# LESR_MainBoard.net
KiCad netlist of a schematic drawn in EAGLE
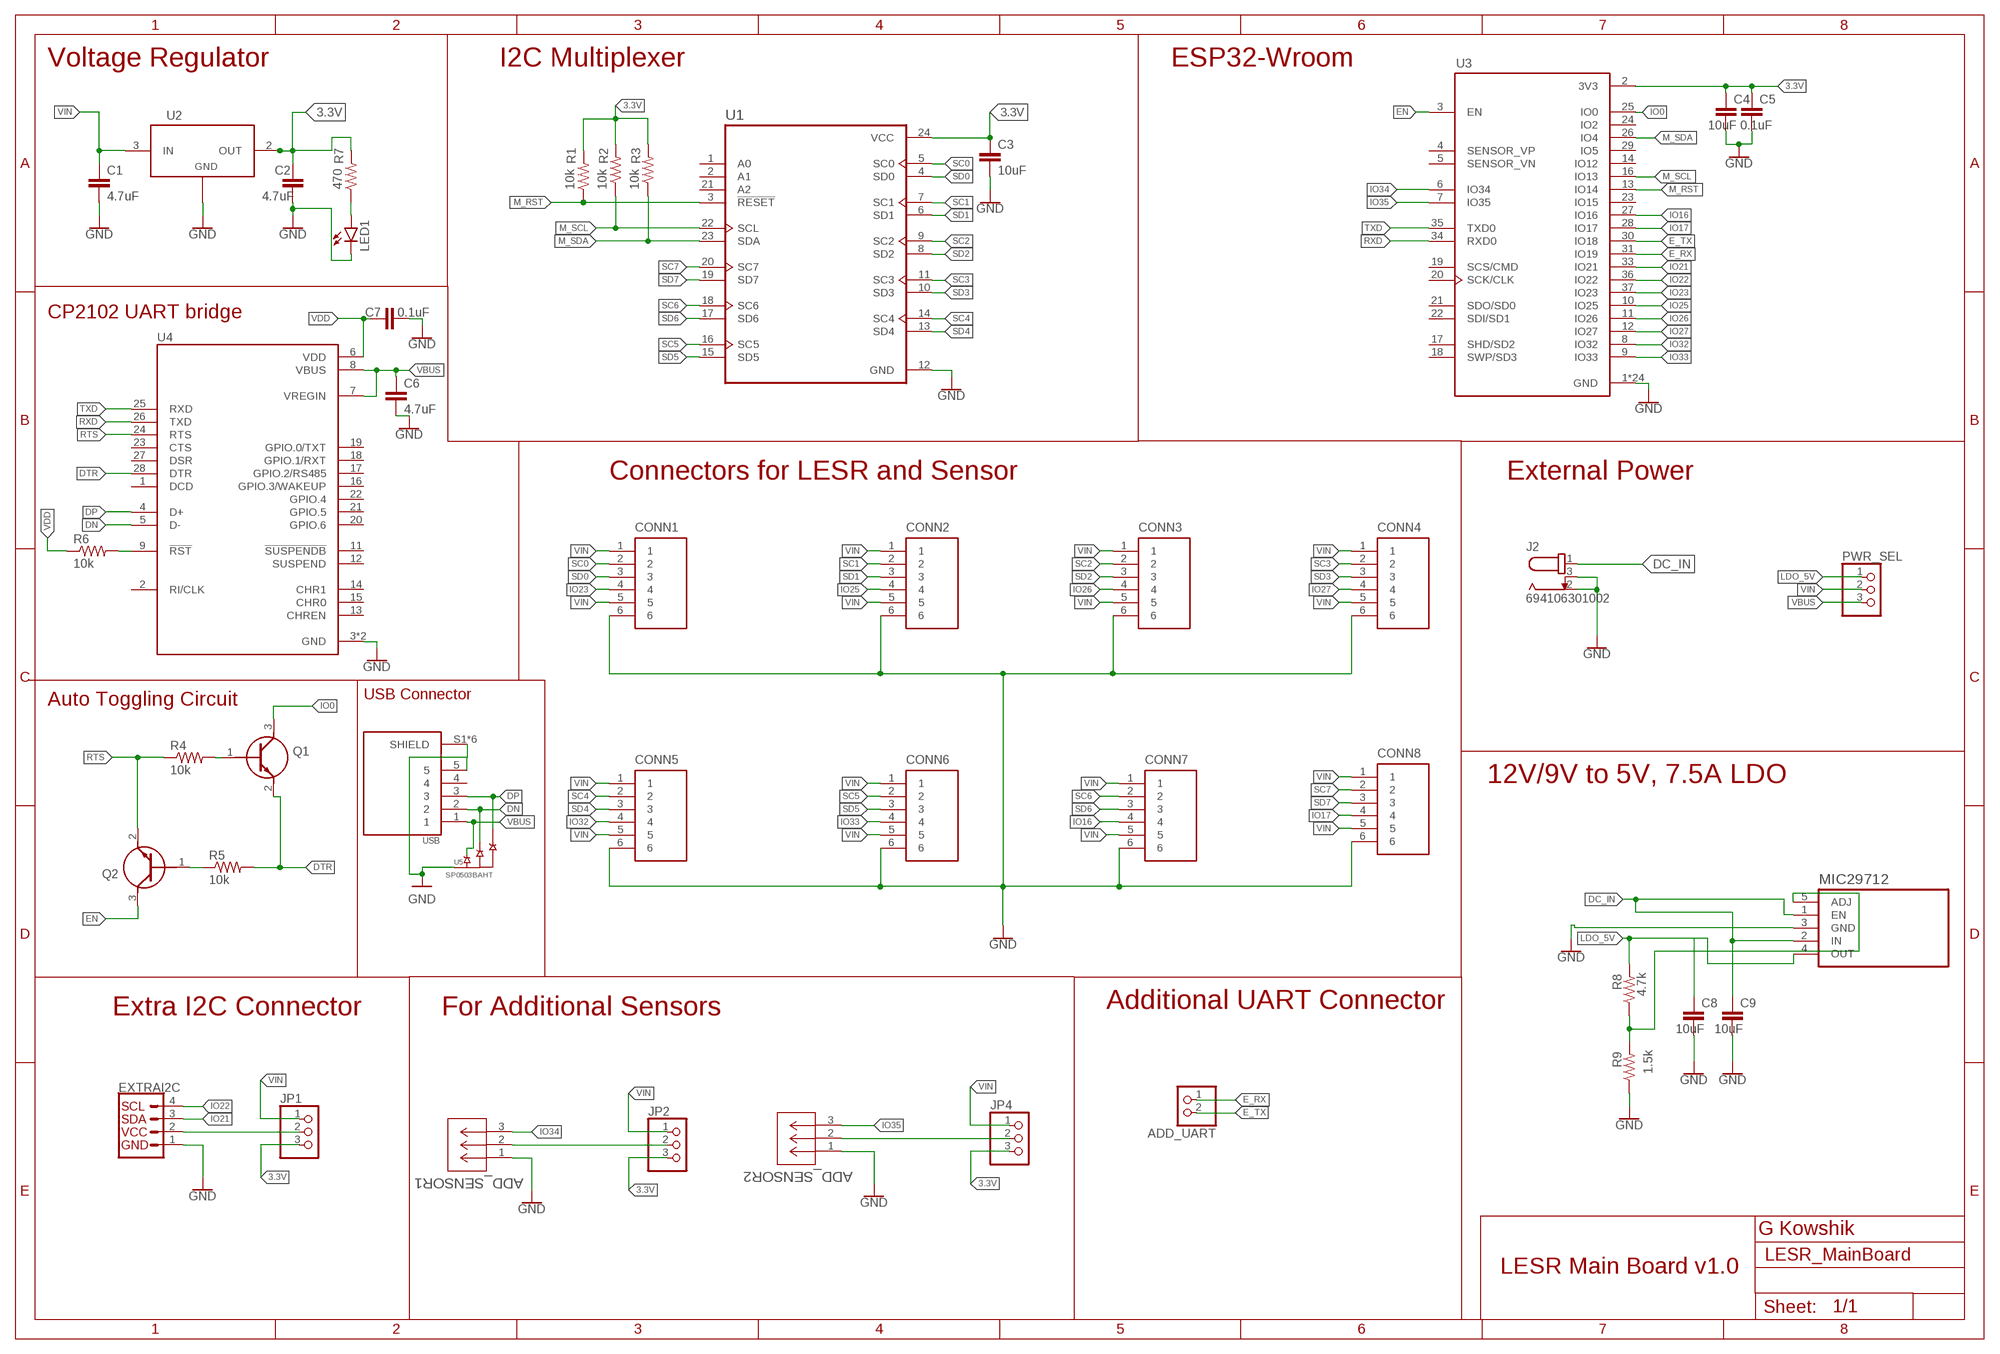
[diagram p0: schematic, sheet 1]

(export (version "E")
  (design (tool "Eeschema 10.0.6"))
  (components
    (comp (ref "ADD_SENSOR1")
      (value "BM03B-SRSS-TB(LF)(SN)")
      (footprint "eagle-import:CONN_BM03B-SRSS-TB(LF)(SN)_JST")
      (fields (field (name "COPYRIGHT") "Copyright (C) 2018 Accelerated Designs. All rights reserved"))
      (libsource (lib "eagle-import") (part "BM03B-SRSS-TB(LF)(SN)"))
    )
    (comp (ref "ADD_SENSOR2")
      (value "BM03B-SRSS-TB(LF)(SN)")
      (footprint "eagle-import:CONN_BM03B-SRSS-TB(LF)(SN)_JST")
      (fields (field (name "COPYRIGHT") "Copyright (C) 2018 Accelerated Designs. All rights reserved"))
      (libsource (lib "eagle-import") (part "BM03B-SRSS-TB(LF)(SN)"))
    )
    (comp (ref "ADD_UART")
      (value "JST_2PIN-SMT")
      (footprint "eagle-import:JST-PH-2-SMT")
      (libsource (lib "eagle-import") (part "JST_2PIN-SMT"))
    )
    (comp (ref "C1")
      (value "4.7uF")
      (footprint "eagle-import:C0805")
      (libsource (lib "eagle-import") (part "C-EUC0805"))
    )
    (comp (ref "C2")
      (value "4.7uF")
      (footprint "eagle-import:C0805")
      (libsource (lib "eagle-import") (part "C-EUC0805"))
    )
    (comp (ref "C3")
      (value "10uF")
      (footprint "eagle-import:C0805")
      (libsource (lib "eagle-import") (part "C-EUC0805"))
    )
    (comp (ref "C4")
      (value "10uF")
      (footprint "eagle-import:C0805")
      (libsource (lib "eagle-import") (part "C-EUC0805"))
    )
    (comp (ref "C5")
      (value "0.1uF")
      (footprint "eagle-import:C0805")
      (libsource (lib "eagle-import") (part "C-EUC0805"))
    )
    (comp (ref "C6")
      (value "4.7uF")
      (footprint "eagle-import:C0805")
      (libsource (lib "eagle-import") (part "C-EUC0805"))
    )
    (comp (ref "C7")
      (value "0.1uF")
      (footprint "eagle-import:C0805")
      (libsource (lib "eagle-import") (part "C-EUC0805"))
    )
    (comp (ref "C8")
      (value "10uF")
      (footprint "eagle-import:C0805")
      (libsource (lib "eagle-import") (part "C-EUC0805"))
    )
    (comp (ref "C9")
      (value "10uF")
      (footprint "eagle-import:C0805")
      (libsource (lib "eagle-import") (part "C-EUC0805"))
    )
    (comp (ref "CONN1")
      (value "JST_6_PIN_VERTICAL")
      (footprint "eagle-import:JST-6-SMD-VERT-1.0MM")
      (libsource (lib "eagle-import") (part "JST_6_PIN_VERTICAL"))
    )
    (comp (ref "CONN2")
      (value "JST_6_PIN_VERTICAL")
      (footprint "eagle-import:JST-6-SMD-VERT-1.0MM")
      (libsource (lib "eagle-import") (part "JST_6_PIN_VERTICAL"))
    )
    (comp (ref "CONN3")
      (value "JST_6_PIN_VERTICAL")
      (footprint "eagle-import:JST-6-SMD-VERT-1.0MM")
      (libsource (lib "eagle-import") (part "JST_6_PIN_VERTICAL"))
    )
    (comp (ref "CONN4")
      (value "JST_6_PIN_VERTICAL")
      (footprint "eagle-import:JST-6-SMD-VERT-1.0MM")
      (libsource (lib "eagle-import") (part "JST_6_PIN_VERTICAL"))
    )
    (comp (ref "CONN5")
      (value "JST_6_PIN_VERTICAL")
      (footprint "eagle-import:JST-6-SMD-VERT-1.0MM")
      (libsource (lib "eagle-import") (part "JST_6_PIN_VERTICAL"))
    )
    (comp (ref "CONN6")
      (value "JST_6_PIN_VERTICAL")
      (footprint "eagle-import:JST-6-SMD-VERT-1.0MM")
      (libsource (lib "eagle-import") (part "JST_6_PIN_VERTICAL"))
    )
    (comp (ref "CONN7")
      (value "JST_6_PIN_VERTICAL")
      (footprint "eagle-import:JST-6-SMD-VERT-1.0MM")
      (libsource (lib "eagle-import") (part "JST_6_PIN_VERTICAL"))
    )
    (comp (ref "CONN8")
      (value "JST_6_PIN_VERTICAL")
      (footprint "eagle-import:JST-6-SMD-VERT-1.0MM")
      (libsource (lib "eagle-import") (part "JST_6_PIN_VERTICAL"))
    )
    (comp (ref "EXTRAI2C")
      (value "Vertical Qwiic Connector")
      (footprint "eagle-import:JST04_1MM_VERT")
      (libsource (lib "eagle-import") (part "QWIIC_CONNECTOR"))
    )
    (comp (ref "J2")
      (value "694106301002")
      (footprint "eagle-import:694106301002")
      (fields
        (field (name "DIGIKEY_PART_NUMBER") "732-5930-ND")
        (field (name "MANUFACTURER") "Wurth Electronics Inc.")
        (field (name "CREATED_BY") "PCBLayout.com")
      )
      (libsource (lib "eagle-import") (part "694106301002"))
    )
    (comp (ref "JP1")
      (value "PINHD-1X3")
      (footprint "eagle-import:1X03")
      (libsource (lib "eagle-import") (part "PINHD-1X3"))
    )
    (comp (ref "JP2")
      (value "PINHD-1X3")
      (footprint "eagle-import:1X03")
      (libsource (lib "eagle-import") (part "PINHD-1X3"))
    )
    (comp (ref "JP4")
      (value "PINHD-1X3")
      (footprint "eagle-import:1X03")
      (libsource (lib "eagle-import") (part "PINHD-1X3"))
    )
    (comp (ref "LED1")
      (value "LEDCHIPLED_0805")
      (footprint "eagle-import:CHIPLED_0805")
      (libsource (lib "eagle-import") (part "LEDCHIPLED_0805"))
    )
    (comp (ref "MIC29712")
      (value "MIC29712WT")
      (footprint "eagle-import:TO170P1066X482X1572-5")
      (fields (field (name "MF") "Microchip"))
      (libsource (lib "eagle-import") (part "MIC29712WT"))
    )
    (comp (ref "PWR_SEL")
      (value "PINHD-1X3")
      (footprint "eagle-import:1X03")
      (libsource (lib "eagle-import") (part "PINHD-1X3"))
    )
    (comp (ref "Q1")
      (value "SS8050-G")
      (footprint "eagle-import:SOT95P240X115-3N")
      (fields (field (name "MF") "Comchip Technology"))
      (libsource (lib "eagle-import") (part "SS8050-G"))
    )
    (comp (ref "Q2")
      (value "SS8050-G")
      (footprint "eagle-import:SOT95P240X115-3N")
      (fields (field (name "MF") "Comchip Technology"))
      (libsource (lib "eagle-import") (part "SS8050-G"))
    )
    (comp (ref "R1")
      (value "10k")
      (footprint "eagle-import:R0805")
      (libsource (lib "eagle-import") (part "R-US_R0805"))
    )
    (comp (ref "R2")
      (value "10k")
      (footprint "eagle-import:R0805")
      (libsource (lib "eagle-import") (part "R-US_R0805"))
    )
    (comp (ref "R3")
      (value "10k")
      (footprint "eagle-import:R0805")
      (libsource (lib "eagle-import") (part "R-US_R0805"))
    )
    (comp (ref "R4")
      (value "10k")
      (footprint "eagle-import:R0805")
      (libsource (lib "eagle-import") (part "R-US_R0805"))
    )
    (comp (ref "R5")
      (value "10k")
      (footprint "eagle-import:R0805")
      (libsource (lib "eagle-import") (part "R-US_R0805"))
    )
    (comp (ref "R6")
      (value "10k")
      (footprint "eagle-import:R0805")
      (libsource (lib "eagle-import") (part "R-US_R0805"))
    )
    (comp (ref "R7")
      (value "470")
      (footprint "eagle-import:R0805")
      (libsource (lib "eagle-import") (part "R-US_R0805"))
    )
    (comp (ref "R8")
      (value "4.7k")
      (footprint "eagle-import:R0805")
      (libsource (lib "eagle-import") (part "R-US_R0805"))
    )
    (comp (ref "R9")
      (value "1.5k")
      (footprint "eagle-import:R0805")
      (libsource (lib "eagle-import") (part "R-US_R0805"))
    )
    (comp (ref "U1")
      (value "TCA9548APWR")
      (footprint "eagle-import:SOP65P640X120-24N")
      (fields (field (name "MF") "Texas Instruments"))
      (libsource (lib "eagle-import") (part "TCA9548APWR"))
    )
    (comp (ref "U2")
      (value "NCP1117ST33T3G")
      (footprint "eagle-import:SOT-223")
      (fields
        (field (name "DIGIKEY_PART_NUMBER") "NCP1117ST33T3GOSTR-ND")
        (field (name "MANUFACTURER") "ON Semiconductor")
        (field (name "CREATED_BY") "PCBLayout.com")
      )
      (libsource (lib "eagle-import") (part "NCP1117ST33T3G"))
    )
    (comp (ref "U3")
      (value "ESP32-WROOM-32")
      (footprint "eagle-import:MODULE_ESP32-WROOM-32")
      (fields (field (name "MF") "Espressif Systems"))
      (libsource (lib "eagle-import") (part "ESP32-WROOM-32"))
    )
    (comp (ref "U4")
      (value "CP2102N-A01-GQFN28")
      (footprint "eagle-import:QFN50P500X500X80-29N")
      (fields (field (name "MF") "Silicon Labs"))
      (libsource (lib "eagle-import") (part "CP2102N-A01-GQFN28"))
    )
    (comp (ref "U5")
      (value "SP0503BAHT")
      (footprint "eagle-import:SOT143")
      (fields (field (name "MF") "Littelfuse Inc."))
      (libsource (lib "eagle-import") (part "SP0503BAHT"))
    )
    (comp (ref "USB")
      (value "10118194-0001LF")
      (footprint "eagle-import:AMPHENOL_10118194-0001LF")
      (fields (field (name "MF") "Amphenol ICC (FCI)"))
      (libsource (lib "eagle-import") (part "10118194-0001LF"))
    )
  )
  (nets
    (net (code "1") (name "3.3V") (class "Default")
      (node (ref "C2") (pin "1") (pinfunction "1_1") (pintype "passive"))
      (node (ref "C3") (pin "1") (pinfunction "1_1") (pintype "passive"))
      (node (ref "C4") (pin "1") (pinfunction "1_1") (pintype "passive"))
      (node (ref "C5") (pin "1") (pinfunction "1_1") (pintype "passive"))
      (node (ref "JP1") (pin "3") (pinfunction "3_3") (pintype "passive"))
      (node (ref "JP2") (pin "3") (pinfunction "3_3") (pintype "passive"))
      (node (ref "JP4") (pin "3") (pinfunction "3_3") (pintype "passive"))
      (node (ref "R1") (pin "2") (pinfunction "2_2") (pintype "passive"))
      (node (ref "R2") (pin "2") (pinfunction "2_2") (pintype "passive"))
      (node (ref "R3") (pin "2") (pinfunction "2_2") (pintype "passive"))
      (node (ref "R7") (pin "2") (pinfunction "2_2") (pintype "passive"))
      (node (ref "U1") (pin "24") (pinfunction "VCC_24") (pintype "power_in"))
      (node (ref "U2") (pin "2") (pinfunction "OUT_2") (pintype "output"))
      (node (ref "U2") (pin "4") (pinfunction "4_4") (pintype "passive"))
      (node (ref "U3") (pin "2") (pinfunction "3V3_2") (pintype "power_in"))
    )
    (net (code "2") (name "DC_IN") (class "Default")
      (node (ref "C9") (pin "1") (pinfunction "1_1") (pintype "passive"))
      (node (ref "J2") (pin "1") (pinfunction "1_1") (pintype "passive"))
      (node (ref "MIC29712") (pin "1") (pinfunction "EN_1") (pintype "input"))
      (node (ref "MIC29712") (pin "2") (pinfunction "IN_2") (pintype "input"))
    )
    (net (code "3") (name "DN") (class "Default")
      (node (ref "U4") (pin "5") (pinfunction "D-_5") (pintype "bidirectional"))
      (node (ref "U5") (pin "3") (pinfunction "B_3") (pintype "bidirectional"))
      (node (ref "USB") (pin "2") (pinfunction "2_2") (pintype "passive"))
    )
    (net (code "4") (name "DP") (class "Default")
      (node (ref "U4") (pin "4") (pinfunction "D+_4") (pintype "bidirectional"))
      (node (ref "U5") (pin "4") (pinfunction "C_4") (pintype "bidirectional"))
      (node (ref "USB") (pin "3") (pinfunction "3_3") (pintype "passive"))
    )
    (net (code "5") (name "DTR") (class "Default")
      (node (ref "Q1") (pin "2") (pinfunction "E_2") (pintype "bidirectional"))
      (node (ref "R5") (pin "2") (pinfunction "2_2") (pintype "passive"))
      (node (ref "U4") (pin "28") (pinfunction "DTR_28") (pintype "output"))
    )
    (net (code "6") (name "EN") (class "Default")
      (node (ref "Q2") (pin "3") (pinfunction "C_3") (pintype "bidirectional"))
      (node (ref "U3") (pin "3") (pinfunction "EN_3") (pintype "input"))
    )
    (net (code "7") (name "E_RX") (class "Default")
      (node (ref "ADD_UART") (pin "1") (pinfunction "2_1") (pintype "passive"))
      (node (ref "U3") (pin "31") (pinfunction "IO19_31") (pintype "bidirectional"))
    )
    (net (code "8") (name "E_TX") (class "Default")
      (node (ref "ADD_UART") (pin "2") (pinfunction "1_2") (pintype "passive"))
      (node (ref "U3") (pin "30") (pinfunction "IO18_30") (pintype "bidirectional"))
    )
    (net (code "9") (name "GND") (class "Default")
      (node (ref "ADD_SENSOR1") (pin "1") (pinfunction "1_1") (pintype "passive"))
      (node (ref "ADD_SENSOR2") (pin "1") (pinfunction "1_1") (pintype "passive"))
      (node (ref "C1") (pin "2") (pinfunction "2_2") (pintype "passive"))
      (node (ref "C2") (pin "2") (pinfunction "2_2") (pintype "passive"))
      (node (ref "C3") (pin "2") (pinfunction "2_2") (pintype "passive"))
      (node (ref "C4") (pin "2") (pinfunction "2_2") (pintype "passive"))
      (node (ref "C5") (pin "2") (pinfunction "2_2") (pintype "passive"))
      (node (ref "C6") (pin "2") (pinfunction "2_2") (pintype "passive"))
      (node (ref "C7") (pin "2") (pinfunction "2_2") (pintype "passive"))
      (node (ref "C8") (pin "2") (pinfunction "2_2") (pintype "passive"))
      (node (ref "C9") (pin "2") (pinfunction "2_2") (pintype "passive"))
      (node (ref "CONN1") (pin "6") (pinfunction "6_6") (pintype "bidirectional"))
      (node (ref "CONN2") (pin "6") (pinfunction "6_6") (pintype "bidirectional"))
      (node (ref "CONN3") (pin "6") (pinfunction "6_6") (pintype "bidirectional"))
      (node (ref "CONN4") (pin "6") (pinfunction "6_6") (pintype "bidirectional"))
      (node (ref "CONN5") (pin "6") (pinfunction "6_6") (pintype "bidirectional"))
      (node (ref "CONN6") (pin "6") (pinfunction "6_6") (pintype "bidirectional"))
      (node (ref "CONN7") (pin "6") (pinfunction "6_6") (pintype "bidirectional"))
      (node (ref "CONN8") (pin "6") (pinfunction "6_6") (pintype "bidirectional"))
      (node (ref "EXTRAI2C") (pin "1") (pinfunction "1_1") (pintype "power_in"))
      (node (ref "J2") (pin "2") (pinfunction "2_2") (pintype "passive"))
      (node (ref "J2") (pin "3") (pinfunction "3_3") (pintype "passive"))
      (node (ref "LED1") (pin "C") (pinfunction "C_C") (pintype "passive"))
      (node (ref "MIC29712") (pin "3") (pinfunction "GND_3") (pintype "input"))
      (node (ref "R9") (pin "1") (pinfunction "1_1") (pintype "passive"))
      (node (ref "U1") (pin "12") (pinfunction "GND_12") (pintype "power_in"))
      (node (ref "U2") (pin "1") (pinfunction "ADJ/GND_1") (pintype "power_in"))
      (node (ref "U3") (pin "1") (pinfunction "GND_1") (pintype "power_in"))
      (node (ref "U3") (pin "15") (pinfunction "GND_15") (pintype "power_in"))
      (node (ref "U3") (pin "38") (pinfunction "GND_38") (pintype "power_in"))
      (node (ref "U3") (pin "39_1") (pinfunction "GND_39_1") (pintype "power_in"))
      (node (ref "U3") (pin "39_10") (pinfunction "GND_39_10") (pintype "power_in"))
      (node (ref "U3") (pin "39_11") (pinfunction "GND_39_11") (pintype "power_in"))
      (node (ref "U3") (pin "39_12") (pinfunction "GND_39_12") (pintype "power_in"))
      (node (ref "U3") (pin "39_13") (pinfunction "GND_39_13") (pintype "power_in"))
      (node (ref "U3") (pin "39_14") (pinfunction "GND_39_14") (pintype "power_in"))
      (node (ref "U3") (pin "39_15") (pinfunction "GND_39_15") (pintype "power_in"))
      (node (ref "U3") (pin "39_16") (pinfunction "GND_39_16") (pintype "power_in"))
      (node (ref "U3") (pin "39_17") (pinfunction "GND_39_17") (pintype "power_in"))
      (node (ref "U3") (pin "39_18") (pinfunction "GND_39_18") (pintype "power_in"))
      (node (ref "U3") (pin "39_19") (pinfunction "GND_39_19") (pintype "power_in"))
      (node (ref "U3") (pin "39_2") (pinfunction "GND_39_2") (pintype "power_in"))
      (node (ref "U3") (pin "39_20") (pinfunction "GND_39_20") (pintype "power_in"))
      (node (ref "U3") (pin "39_21") (pinfunction "GND_39_21") (pintype "power_in"))
      (node (ref "U3") (pin "39_3") (pinfunction "GND_39_3") (pintype "power_in"))
      (node (ref "U3") (pin "39_4") (pinfunction "GND_39_4") (pintype "power_in"))
      (node (ref "U3") (pin "39_5") (pinfunction "GND_39_5") (pintype "power_in"))
      (node (ref "U3") (pin "39_6") (pinfunction "GND_39_6") (pintype "power_in"))
      (node (ref "U3") (pin "39_7") (pinfunction "GND_39_7") (pintype "power_in"))
      (node (ref "U3") (pin "39_8") (pinfunction "GND_39_8") (pintype "power_in"))
      (node (ref "U3") (pin "39_9") (pinfunction "GND_39_9") (pintype "power_in"))
      (node (ref "U4") (pin "29") (pinfunction "GND_29") (pintype "power_in"))
      (node (ref "U4") (pin "3") (pinfunction "GND_3") (pintype "power_in"))
      (node (ref "U5") (pin "1") (pinfunction "GND_1") (pintype "bidirectional"))
      (node (ref "USB") (pin "5") (pinfunction "5_5") (pintype "passive"))
      (node (ref "USB") (pin "S1") (pinfunction "SHIELD_S1") (pintype "passive"))
      (node (ref "USB") (pin "S2") (pinfunction "SHIELD_S2") (pintype "passive"))
      (node (ref "USB") (pin "S3") (pinfunction "SHIELD_S3") (pintype "passive"))
      (node (ref "USB") (pin "S4") (pinfunction "SHIELD_S4") (pintype "passive"))
      (node (ref "USB") (pin "S5") (pinfunction "SHIELD_S5") (pintype "passive"))
      (node (ref "USB") (pin "S6") (pinfunction "SHIELD_S6") (pintype "passive"))
    )
    (net (code "10") (name "IO0") (class "Default")
      (node (ref "Q1") (pin "3") (pinfunction "C_3") (pintype "bidirectional"))
      (node (ref "U3") (pin "25") (pinfunction "IO0_25") (pintype "bidirectional"))
    )
    (net (code "11") (name "IO16") (class "Default")
      (node (ref "CONN7") (pin "4") (pinfunction "4_4") (pintype "bidirectional"))
      (node (ref "U3") (pin "27") (pinfunction "IO16_27") (pintype "bidirectional"))
    )
    (net (code "12") (name "IO17") (class "Default")
      (node (ref "CONN8") (pin "4") (pinfunction "4_4") (pintype "bidirectional"))
      (node (ref "U3") (pin "28") (pinfunction "IO17_28") (pintype "bidirectional"))
    )
    (net (code "13") (name "IO21") (class "Default")
      (node (ref "EXTRAI2C") (pin "3") (pinfunction "3_3") (pintype "passive"))
      (node (ref "U3") (pin "33") (pinfunction "IO21_33") (pintype "bidirectional"))
    )
    (net (code "14") (name "IO22") (class "Default")
      (node (ref "EXTRAI2C") (pin "4") (pinfunction "4_4") (pintype "passive"))
      (node (ref "U3") (pin "36") (pinfunction "IO22_36") (pintype "bidirectional"))
    )
    (net (code "15") (name "IO23") (class "Default")
      (node (ref "CONN1") (pin "4") (pinfunction "4_4") (pintype "bidirectional"))
      (node (ref "U3") (pin "37") (pinfunction "IO23_37") (pintype "bidirectional"))
    )
    (net (code "16") (name "IO25") (class "Default")
      (node (ref "CONN2") (pin "4") (pinfunction "4_4") (pintype "bidirectional"))
      (node (ref "U3") (pin "10") (pinfunction "IO25_10") (pintype "bidirectional"))
    )
    (net (code "17") (name "IO26") (class "Default")
      (node (ref "CONN3") (pin "4") (pinfunction "4_4") (pintype "bidirectional"))
      (node (ref "U3") (pin "11") (pinfunction "IO26_11") (pintype "bidirectional"))
    )
    (net (code "18") (name "IO27") (class "Default")
      (node (ref "CONN4") (pin "4") (pinfunction "4_4") (pintype "bidirectional"))
      (node (ref "U3") (pin "12") (pinfunction "IO27_12") (pintype "bidirectional"))
    )
    (net (code "19") (name "IO32") (class "Default")
      (node (ref "CONN5") (pin "4") (pinfunction "4_4") (pintype "bidirectional"))
      (node (ref "U3") (pin "8") (pinfunction "IO32_8") (pintype "bidirectional"))
    )
    (net (code "20") (name "IO33") (class "Default")
      (node (ref "CONN6") (pin "4") (pinfunction "4_4") (pintype "bidirectional"))
      (node (ref "U3") (pin "9") (pinfunction "IO33_9") (pintype "bidirectional"))
    )
    (net (code "21") (name "IO34") (class "Default")
      (node (ref "ADD_SENSOR1") (pin "3") (pinfunction "3_3") (pintype "passive"))
      (node (ref "U3") (pin "6") (pinfunction "IO34_6") (pintype "input"))
    )
    (net (code "22") (name "IO35") (class "Default")
      (node (ref "ADD_SENSOR2") (pin "3") (pinfunction "3_3") (pintype "passive"))
      (node (ref "U3") (pin "7") (pinfunction "IO35_7") (pintype "input"))
    )
    (net (code "23") (name "LDO_5V") (class "Default")
      (node (ref "C8") (pin "1") (pinfunction "1_1") (pintype "passive"))
      (node (ref "MIC29712") (pin "4") (pinfunction "OUT_4") (pintype "input"))
      (node (ref "PWR_SEL") (pin "1") (pinfunction "1_1") (pintype "passive"))
      (node (ref "R8") (pin "2") (pinfunction "2_2") (pintype "passive"))
    )
    (net (code "24") (name "M_RST") (class "Default")
      (node (ref "R1") (pin "1") (pinfunction "1_1") (pintype "passive"))
      (node (ref "U1") (pin "3") (pinfunction "~{RESET}_3") (pintype "input"))
      (node (ref "U3") (pin "13") (pinfunction "IO14_13") (pintype "bidirectional"))
    )
    (net (code "25") (name "M_SCL") (class "Default")
      (node (ref "R2") (pin "1") (pinfunction "1_1") (pintype "passive"))
      (node (ref "U1") (pin "22") (pinfunction "SCL_22") (pintype "bidirectional"))
      (node (ref "U3") (pin "16") (pinfunction "IO13_16") (pintype "bidirectional"))
    )
    (net (code "26") (name "M_SDA") (class "Default")
      (node (ref "R3") (pin "1") (pinfunction "1_1") (pintype "passive"))
      (node (ref "U1") (pin "23") (pinfunction "SDA_23") (pintype "bidirectional"))
      (node (ref "U3") (pin "26") (pinfunction "IO4_26") (pintype "bidirectional"))
    )
    (net (code "27") (name "Net-(ADD_SENSOR1-Pad2)") (class "Default")
      (node (ref "ADD_SENSOR1") (pin "2") (pinfunction "2_2") (pintype "passive"))
      (node (ref "JP2") (pin "2") (pinfunction "2_2") (pintype "passive"))
    )
    (net (code "28") (name "Net-(ADD_SENSOR2-Pad2)") (class "Default")
      (node (ref "ADD_SENSOR2") (pin "2") (pinfunction "2_2") (pintype "passive"))
      (node (ref "JP4") (pin "2") (pinfunction "2_2") (pintype "passive"))
    )
    (net (code "29") (name "Net-(EXTRAI2C-Pad2)") (class "Default")
      (node (ref "EXTRAI2C") (pin "2") (pinfunction "2_2") (pintype "power_in"))
      (node (ref "JP1") (pin "2") (pinfunction "2_2") (pintype "passive"))
    )
    (net (code "30") (name "Net-(LED1-PadA)") (class "Default")
      (node (ref "LED1") (pin "A") (pinfunction "A_A") (pintype "passive"))
      (node (ref "R7") (pin "1") (pinfunction "1_1") (pintype "passive"))
    )
    (net (code "31") (name "Net-(MIC29712-ADJ)") (class "Default")
      (node (ref "MIC29712") (pin "5") (pinfunction "ADJ_5") (pintype "input"))
      (node (ref "R8") (pin "1") (pinfunction "1_1") (pintype "passive"))
      (node (ref "R9") (pin "2") (pinfunction "2_2") (pintype "passive"))
    )
    (net (code "32") (name "Net-(Q1-B)") (class "Default")
      (node (ref "Q1") (pin "1") (pinfunction "B_1") (pintype "bidirectional"))
      (node (ref "R4") (pin "2") (pinfunction "2_2") (pintype "passive"))
    )
    (net (code "33") (name "Net-(Q2-B)") (class "Default")
      (node (ref "Q2") (pin "1") (pinfunction "B_1") (pintype "bidirectional"))
      (node (ref "R5") (pin "1") (pinfunction "1_1") (pintype "passive"))
    )
    (net (code "34") (name "Net-(U4-~{RST})") (class "Default")
      (node (ref "R6") (pin "2") (pinfunction "2_2") (pintype "passive"))
      (node (ref "U4") (pin "9") (pinfunction "~{RST}_9") (pintype "input"))
    )
    (net (code "35") (name "RTS") (class "Default")
      (node (ref "Q2") (pin "2") (pinfunction "E_2") (pintype "bidirectional"))
      (node (ref "R4") (pin "1") (pinfunction "1_1") (pintype "passive"))
      (node (ref "U4") (pin "24") (pinfunction "RTS_24") (pintype "output"))
    )
    (net (code "36") (name "RXD") (class "Default")
      (node (ref "U3") (pin "34") (pinfunction "RXD0_34") (pintype "bidirectional"))
      (node (ref "U4") (pin "26") (pinfunction "TXD_26") (pintype "output"))
    )
    (net (code "37") (name "SC0") (class "Default")
      (node (ref "CONN1") (pin "2") (pinfunction "2_2") (pintype "bidirectional"))
      (node (ref "U1") (pin "5") (pinfunction "SC0_5") (pintype "bidirectional"))
    )
    (net (code "38") (name "SC1") (class "Default")
      (node (ref "CONN2") (pin "2") (pinfunction "2_2") (pintype "bidirectional"))
      (node (ref "U1") (pin "7") (pinfunction "SC1_7") (pintype "bidirectional"))
    )
    (net (code "39") (name "SC2") (class "Default")
      (node (ref "CONN3") (pin "2") (pinfunction "2_2") (pintype "bidirectional"))
      (node (ref "U1") (pin "9") (pinfunction "SC2_9") (pintype "bidirectional"))
    )
    (net (code "40") (name "SC3") (class "Default")
      (node (ref "CONN4") (pin "2") (pinfunction "2_2") (pintype "bidirectional"))
      (node (ref "U1") (pin "11") (pinfunction "SC3_11") (pintype "bidirectional"))
    )
    (net (code "41") (name "SC4") (class "Default")
      (node (ref "CONN5") (pin "2") (pinfunction "2_2") (pintype "bidirectional"))
      (node (ref "U1") (pin "14") (pinfunction "SC4_14") (pintype "bidirectional"))
    )
    (net (code "42") (name "SC5") (class "Default")
      (node (ref "CONN6") (pin "2") (pinfunction "2_2") (pintype "bidirectional"))
      (node (ref "U1") (pin "16") (pinfunction "SC5_16") (pintype "bidirectional"))
    )
    (net (code "43") (name "SC6") (class "Default")
      (node (ref "CONN7") (pin "2") (pinfunction "2_2") (pintype "bidirectional"))
      (node (ref "U1") (pin "18") (pinfunction "SC6_18") (pintype "bidirectional"))
    )
    (net (code "44") (name "SC7") (class "Default")
      (node (ref "CONN8") (pin "2") (pinfunction "2_2") (pintype "bidirectional"))
      (node (ref "U1") (pin "20") (pinfunction "SC7_20") (pintype "bidirectional"))
    )
    (net (code "45") (name "SD0") (class "Default")
      (node (ref "CONN1") (pin "3") (pinfunction "3_3") (pintype "bidirectional"))
      (node (ref "U1") (pin "4") (pinfunction "SD0_4") (pintype "bidirectional"))
    )
    (net (code "46") (name "SD1") (class "Default")
      (node (ref "CONN2") (pin "3") (pinfunction "3_3") (pintype "bidirectional"))
      (node (ref "U1") (pin "6") (pinfunction "SD1_6") (pintype "bidirectional"))
    )
    (net (code "47") (name "SD2") (class "Default")
      (node (ref "CONN3") (pin "3") (pinfunction "3_3") (pintype "bidirectional"))
      (node (ref "U1") (pin "8") (pinfunction "SD2_8") (pintype "bidirectional"))
    )
    (net (code "48") (name "SD3") (class "Default")
      (node (ref "CONN4") (pin "3") (pinfunction "3_3") (pintype "bidirectional"))
      (node (ref "U1") (pin "10") (pinfunction "SD3_10") (pintype "bidirectional"))
    )
    (net (code "49") (name "SD4") (class "Default")
      (node (ref "CONN5") (pin "3") (pinfunction "3_3") (pintype "bidirectional"))
      (node (ref "U1") (pin "13") (pinfunction "SD4_13") (pintype "bidirectional"))
    )
    (net (code "50") (name "SD5") (class "Default")
      (node (ref "CONN6") (pin "3") (pinfunction "3_3") (pintype "bidirectional"))
      (node (ref "U1") (pin "15") (pinfunction "SD5_15") (pintype "bidirectional"))
    )
    (net (code "51") (name "SD6") (class "Default")
      (node (ref "CONN7") (pin "3") (pinfunction "3_3") (pintype "bidirectional"))
      (node (ref "U1") (pin "17") (pinfunction "SD6_17") (pintype "bidirectional"))
    )
    (net (code "52") (name "SD7") (class "Default")
      (node (ref "CONN8") (pin "3") (pinfunction "3_3") (pintype "bidirectional"))
      (node (ref "U1") (pin "19") (pinfunction "SD7_19") (pintype "bidirectional"))
    )
    (net (code "53") (name "TXD") (class "Default")
      (node (ref "U3") (pin "35") (pinfunction "TXD0_35") (pintype "bidirectional"))
      (node (ref "U4") (pin "25") (pinfunction "RXD_25") (pintype "input"))
    )
    (net (code "54") (name "VBUS") (class "Default")
      (node (ref "C6") (pin "1") (pinfunction "1_1") (pintype "passive"))
      (node (ref "PWR_SEL") (pin "3") (pinfunction "3_3") (pintype "passive"))
      (node (ref "U4") (pin "7") (pinfunction "VREGIN_7") (pintype "power_in"))
      (node (ref "U4") (pin "8") (pinfunction "VBUS_8") (pintype "power_in"))
      (node (ref "U5") (pin "2") (pinfunction "A_2") (pintype "bidirectional"))
      (node (ref "USB") (pin "1") (pinfunction "1_1") (pintype "passive"))
    )
    (net (code "55") (name "VDD") (class "Default")
      (node (ref "C7") (pin "1") (pinfunction "1_1") (pintype "passive"))
      (node (ref "R6") (pin "1") (pinfunction "1_1") (pintype "passive"))
      (node (ref "U4") (pin "6") (pinfunction "VDD_6") (pintype "power_in"))
    )
    (net (code "56") (name "VIN") (class "Default")
      (node (ref "C1") (pin "1") (pinfunction "1_1") (pintype "passive"))
      (node (ref "CONN1") (pin "1") (pinfunction "1_1") (pintype "bidirectional"))
      (node (ref "CONN1") (pin "5") (pinfunction "5_5") (pintype "bidirectional"))
      (node (ref "CONN2") (pin "1") (pinfunction "1_1") (pintype "bidirectional"))
      (node (ref "CONN2") (pin "5") (pinfunction "5_5") (pintype "bidirectional"))
      (node (ref "CONN3") (pin "1") (pinfunction "1_1") (pintype "bidirectional"))
      (node (ref "CONN3") (pin "5") (pinfunction "5_5") (pintype "bidirectional"))
      (node (ref "CONN4") (pin "1") (pinfunction "1_1") (pintype "bidirectional"))
      (node (ref "CONN4") (pin "5") (pinfunction "5_5") (pintype "bidirectional"))
      (node (ref "CONN5") (pin "1") (pinfunction "1_1") (pintype "bidirectional"))
      (node (ref "CONN5") (pin "5") (pinfunction "5_5") (pintype "bidirectional"))
      (node (ref "CONN6") (pin "1") (pinfunction "1_1") (pintype "bidirectional"))
      (node (ref "CONN6") (pin "5") (pinfunction "5_5") (pintype "bidirectional"))
      (node (ref "CONN7") (pin "1") (pinfunction "1_1") (pintype "bidirectional"))
      (node (ref "CONN7") (pin "5") (pinfunction "5_5") (pintype "bidirectional"))
      (node (ref "CONN8") (pin "1") (pinfunction "1_1") (pintype "bidirectional"))
      (node (ref "CONN8") (pin "5") (pinfunction "5_5") (pintype "bidirectional"))
      (node (ref "JP1") (pin "1") (pinfunction "1_1") (pintype "passive"))
      (node (ref "JP2") (pin "1") (pinfunction "1_1") (pintype "passive"))
      (node (ref "JP4") (pin "1") (pinfunction "1_1") (pintype "passive"))
      (node (ref "PWR_SEL") (pin "2") (pinfunction "2_2") (pintype "passive"))
      (node (ref "U2") (pin "3") (pinfunction "IN_3") (pintype "input"))
    )
    (net (code "57") (name "unconnected-(U1-A0-Pad1)") (class "Default")
      (node (ref "U1") (pin "1") (pinfunction "A0_1") (pintype "input"))
    )
    (net (code "58") (name "unconnected-(U1-A1-Pad2)") (class "Default")
      (node (ref "U1") (pin "2") (pinfunction "A1_2") (pintype "input"))
    )
    (net (code "59") (name "unconnected-(U1-A2-Pad21)") (class "Default")
      (node (ref "U1") (pin "21") (pinfunction "A2_21") (pintype "input"))
    )
    (net (code "60") (name "unconnected-(U3-IO2-Pad24)") (class "Default")
      (node (ref "U3") (pin "24") (pinfunction "IO2_24") (pintype "bidirectional"))
    )
    (net (code "61") (name "unconnected-(U3-IO5-Pad29)") (class "Default")
      (node (ref "U3") (pin "29") (pinfunction "IO5_29") (pintype "bidirectional"))
    )
    (net (code "62") (name "unconnected-(U3-IO12-Pad14)") (class "Default")
      (node (ref "U3") (pin "14") (pinfunction "IO12_14") (pintype "bidirectional"))
    )
    (net (code "63") (name "unconnected-(U3-IO15-Pad23)") (class "Default")
      (node (ref "U3") (pin "23") (pinfunction "IO15_23") (pintype "bidirectional"))
    )
    (net (code "64") (name "unconnected-(U3-SCK{slash}CLK-Pad20)") (class "Default")
      (node (ref "U3") (pin "20") (pinfunction "SCK/CLK_20") (pintype "bidirectional"))
    )
    (net (code "65") (name "unconnected-(U3-SCS{slash}CMD-Pad19)") (class "Default")
      (node (ref "U3") (pin "19") (pinfunction "SCS/CMD_19") (pintype "bidirectional"))
    )
    (net (code "66") (name "unconnected-(U3-SDI{slash}SD1-Pad22)") (class "Default")
      (node (ref "U3") (pin "22") (pinfunction "SDI/SD1_22") (pintype "bidirectional"))
    )
    (net (code "67") (name "unconnected-(U3-SDO{slash}SD0-Pad21)") (class "Default")
      (node (ref "U3") (pin "21") (pinfunction "SDO/SD0_21") (pintype "bidirectional"))
    )
    (net (code "68") (name "unconnected-(U3-SENSOR_VN-Pad5)") (class "Default")
      (node (ref "U3") (pin "5") (pinfunction "SENSOR_VN_5") (pintype "input"))
    )
    (net (code "69") (name "unconnected-(U3-SENSOR_VP-Pad4)") (class "Default")
      (node (ref "U3") (pin "4") (pinfunction "SENSOR_VP_4") (pintype "input"))
    )
    (net (code "70") (name "unconnected-(U3-SHD{slash}SD2-Pad17)") (class "Default")
      (node (ref "U3") (pin "17") (pinfunction "SHD/SD2_17") (pintype "bidirectional"))
    )
    (net (code "71") (name "unconnected-(U3-SWP{slash}SD3-Pad18)") (class "Default")
      (node (ref "U3") (pin "18") (pinfunction "SWP/SD3_18") (pintype "bidirectional"))
    )
    (net (code "72") (name "unconnected-(U4-CHR0-Pad15)") (class "Default")
      (node (ref "U4") (pin "15") (pinfunction "CHR0_15") (pintype "output"))
    )
    (net (code "73") (name "unconnected-(U4-CHR1-Pad14)") (class "Default")
      (node (ref "U4") (pin "14") (pinfunction "CHR1_14") (pintype "output"))
    )
    (net (code "74") (name "unconnected-(U4-CHREN-Pad13)") (class "Default")
      (node (ref "U4") (pin "13") (pinfunction "CHREN_13") (pintype "output"))
    )
    (net (code "75") (name "unconnected-(U4-CTS-Pad23)") (class "Default")
      (node (ref "U4") (pin "23") (pinfunction "CTS_23") (pintype "input"))
    )
    (net (code "76") (name "unconnected-(U4-DCD-Pad1)") (class "Default")
      (node (ref "U4") (pin "1") (pinfunction "DCD_1") (pintype "input"))
    )
    (net (code "77") (name "unconnected-(U4-DSR-Pad27)") (class "Default")
      (node (ref "U4") (pin "27") (pinfunction "DSR_27") (pintype "input"))
    )
    (net (code "78") (name "unconnected-(U4-GPIO.0{slash}TXT-Pad19)") (class "Default")
      (node (ref "U4") (pin "19") (pinfunction "GPIO.0/TXT_19") (pintype "bidirectional"))
    )
    (net (code "79") (name "unconnected-(U4-GPIO.1{slash}RXT-Pad18)") (class "Default")
      (node (ref "U4") (pin "18") (pinfunction "GPIO.1/RXT_18") (pintype "bidirectional"))
    )
    (net (code "80") (name "unconnected-(U4-GPIO.2{slash}RS485-Pad17)") (class "Default")
      (node (ref "U4") (pin "17") (pinfunction "GPIO.2/RS485_17") (pintype "bidirectional"))
    )
    (net (code "81") (name "unconnected-(U4-GPIO.3{slash}WAKEUP-Pad16)") (class "Default")
      (node (ref "U4") (pin "16") (pinfunction "GPIO.3/WAKEUP_16") (pintype "bidirectional"))
    )
    (net (code "82") (name "unconnected-(U4-GPIO.4-Pad22)") (class "Default")
      (node (ref "U4") (pin "22") (pinfunction "GPIO.4_22") (pintype "bidirectional"))
    )
    (net (code "83") (name "unconnected-(U4-GPIO.5-Pad21)") (class "Default")
      (node (ref "U4") (pin "21") (pinfunction "GPIO.5_21") (pintype "bidirectional"))
    )
    (net (code "84") (name "unconnected-(U4-GPIO.6-Pad20)") (class "Default")
      (node (ref "U4") (pin "20") (pinfunction "GPIO.6_20") (pintype "bidirectional"))
    )
    (net (code "85") (name "unconnected-(U4-RI{slash}CLK-Pad2)") (class "Default")
      (node (ref "U4") (pin "2") (pinfunction "RI/CLK_2") (pintype "bidirectional"))
    )
    (net (code "86") (name "unconnected-(U4-SUSPEND-Pad12)") (class "Default")
      (node (ref "U4") (pin "12") (pinfunction "SUSPEND_12") (pintype "output"))
    )
    (net (code "87") (name "unconnected-(U4-~{SUSPENDB}-Pad11)") (class "Default")
      (node (ref "U4") (pin "11") (pinfunction "~{SUSPENDB}_11") (pintype "output"))
    )
    (net (code "88") (name "unconnected-(USB-Pad4)") (class "Default")
      (node (ref "USB") (pin "4") (pinfunction "4_4") (pintype "passive"))
    )
  )
)
